# ChipStomp_v1_1.net
KiCad netlist of a schematic drawn in EAGLE
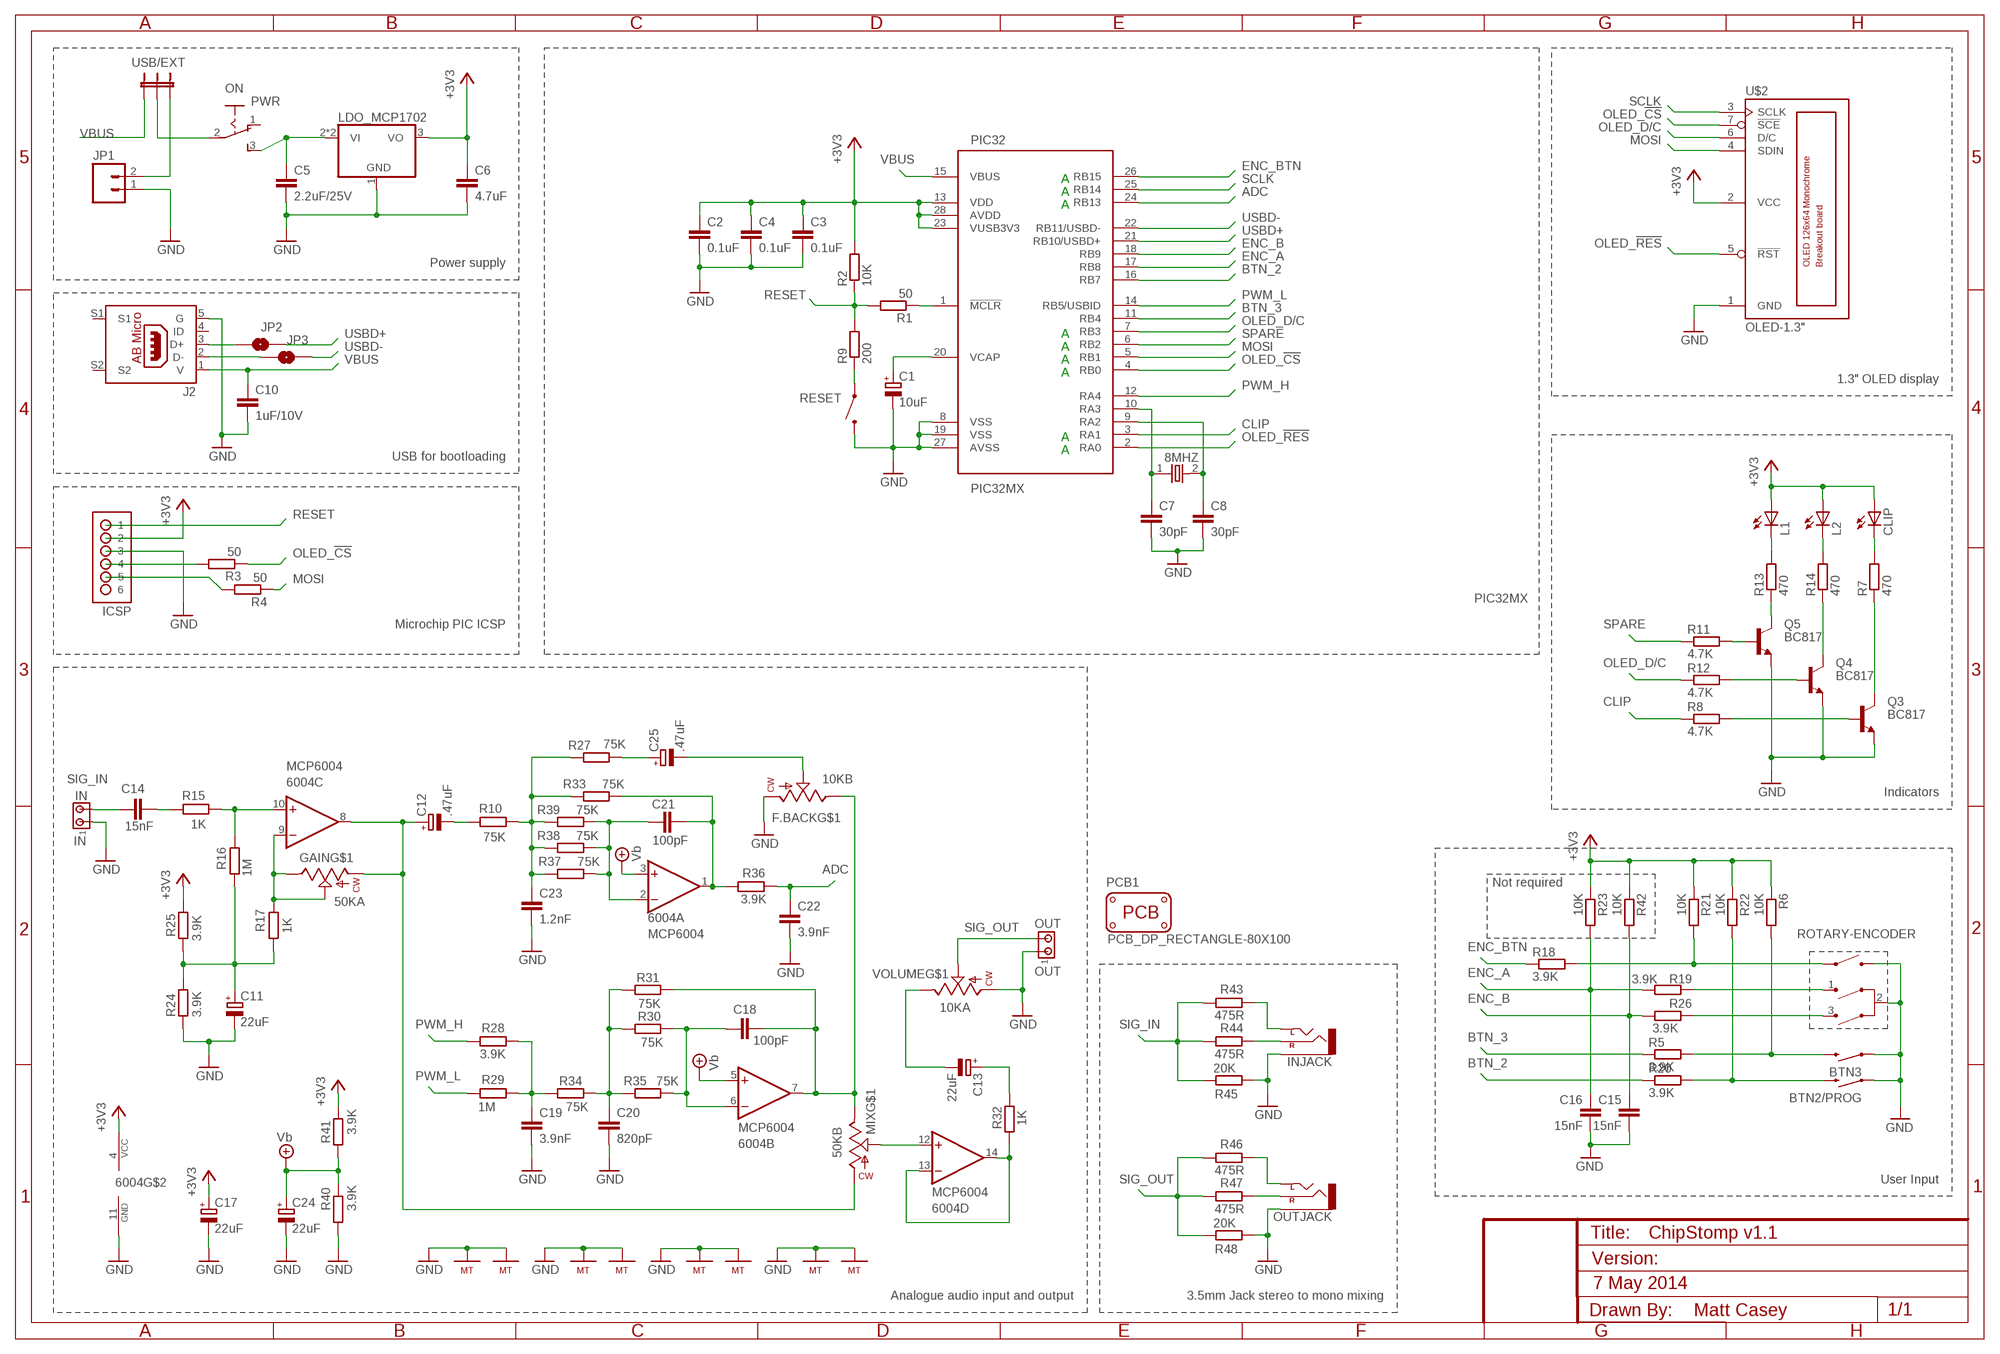
[diagram p0: schematic, sheet 1]

(export (version "E")
  (design (tool "Eeschema 10.0.6"))
  (components
    (comp (ref "8MHZ")
      (value "OSC-XTAL-HC-49U-SMD")
      (footprint "eagle-import:HC-49U")
      (libsource (lib "eagle-import") (part "OSC-XTAL-HC-49U-SMD"))
    )
    (comp (ref "6004")
      (value "MCP6004")
      (footprint "eagle-import:SO-14")
      (libsource (lib "eagle-import") (part "MCP6004"))
    )
    (comp (ref "BTN2/PROG")
      (value "SWITCH-MOMENTARY-212MM")
      (footprint "eagle-import:TACTILE-PTH-12MM")
      (libsource (lib "eagle-import") (part "SWITCH-MOMENTARY-212MM"))
    )
    (comp (ref "BTN3")
      (value "SWITCH-MOMENTARY-212MM")
      (footprint "eagle-import:TACTILE-PTH-12MM")
      (libsource (lib "eagle-import") (part "SWITCH-MOMENTARY-212MM"))
    )
    (comp (ref "C1")
      (value "10uF")
      (footprint "eagle-import:A_3216-18R")
      (libsource (lib "eagle-import") (part "CPOL-EUA/3216-18R"))
    )
    (comp (ref "C2")
      (value "0.1uF")
      (footprint "eagle-import:C0805K")
      (libsource (lib "eagle-import") (part "C-EUC0805K"))
    )
    (comp (ref "C3")
      (value "0.1uF")
      (footprint "eagle-import:C0805K")
      (libsource (lib "eagle-import") (part "C-EUC0805K"))
    )
    (comp (ref "C4")
      (value "0.1uF")
      (footprint "eagle-import:C0805K")
      (libsource (lib "eagle-import") (part "C-EUC0805K"))
    )
    (comp (ref "C5")
      (value "2.2uF/25V")
      (footprint "eagle-import:C0805K")
      (libsource (lib "eagle-import") (part "C-EUC0805K"))
    )
    (comp (ref "C6")
      (value "4.7uF")
      (footprint "eagle-import:C0805K")
      (libsource (lib "eagle-import") (part "C-EUC0805K"))
    )
    (comp (ref "C7")
      (value "30pF")
      (footprint "eagle-import:C0805K")
      (libsource (lib "eagle-import") (part "C-EUC0805K"))
    )
    (comp (ref "C8")
      (value "30pF")
      (footprint "eagle-import:C0805K")
      (libsource (lib "eagle-import") (part "C-EUC0805K"))
    )
    (comp (ref "C10")
      (value "1uF/10V")
      (footprint "eagle-import:C0805K")
      (libsource (lib "eagle-import") (part "C-EUC0805K"))
    )
    (comp (ref "C11")
      (value "22uF")
      (footprint "eagle-import:153CLV-0505")
      (libsource (lib "eagle-import") (part "CPOL-EU153CLV-0505"))
    )
    (comp (ref "C12")
      (value ".47uF")
      (footprint "eagle-import:153CLV-0405")
      (libsource (lib "eagle-import") (part "CPOL-EU153CLV-0405"))
    )
    (comp (ref "C13")
      (value "22uF")
      (footprint "eagle-import:153CLV-0505")
      (libsource (lib "eagle-import") (part "CPOL-EU153CLV-0505"))
    )
    (comp (ref "C14")
      (value "15nF")
      (footprint "eagle-import:C0805K")
      (libsource (lib "eagle-import") (part "C-EUC0805K"))
    )
    (comp (ref "C15")
      (value "15nF")
      (footprint "eagle-import:C0805K")
      (libsource (lib "eagle-import") (part "C-EUC0805K"))
    )
    (comp (ref "C16")
      (value "15nF")
      (footprint "eagle-import:C0805K")
      (libsource (lib "eagle-import") (part "C-EUC0805K"))
    )
    (comp (ref "C17")
      (value "22uF")
      (footprint "eagle-import:153CLV-0505")
      (libsource (lib "eagle-import") (part "CPOL-EU153CLV-0505"))
    )
    (comp (ref "C18")
      (value "100pF")
      (footprint "eagle-import:C0805K")
      (libsource (lib "eagle-import") (part "C-EUC0805K"))
    )
    (comp (ref "C19")
      (value "3.9nF")
      (footprint "eagle-import:C0805K")
      (libsource (lib "eagle-import") (part "C-EUC0805K"))
    )
    (comp (ref "C20")
      (value "820pF")
      (footprint "eagle-import:C0805K")
      (libsource (lib "eagle-import") (part "C-EUC0805K"))
    )
    (comp (ref "C21")
      (value "100pF")
      (footprint "eagle-import:C0805K")
      (libsource (lib "eagle-import") (part "C-EUC0805K"))
    )
    (comp (ref "C22")
      (value "3.9nF")
      (footprint "eagle-import:C0805K")
      (libsource (lib "eagle-import") (part "C-EUC0805K"))
    )
    (comp (ref "C23")
      (value "1.2nF")
      (footprint "eagle-import:C0805K")
      (libsource (lib "eagle-import") (part "C-EUC0805K"))
    )
    (comp (ref "C24")
      (value "22uF")
      (footprint "eagle-import:153CLV-0505")
      (libsource (lib "eagle-import") (part "CPOL-EU153CLV-0505"))
    )
    (comp (ref "C25")
      (value ".47uF")
      (footprint "eagle-import:153CLV-0405")
      (libsource (lib "eagle-import") (part "CPOL-EU153CLV-0405"))
    )
    (comp (ref "CLIP")
      (value "LED-0805")
      (footprint "eagle-import:LED-805")
      (libsource (lib "eagle-import") (part "LED-0805"))
    )
    (comp (ref "F.BACK")
      (value "10KB")
      (footprint "eagle-import:POT_SINGLE_PANASONIC_VERT")
      (libsource (lib "eagle-import") (part "POT"))
    )
    (comp (ref "GAIN")
      (value "50KA")
      (footprint "eagle-import:POT_SINGLE_PANASONIC_VERT")
      (libsource (lib "eagle-import") (part "POT"))
    )
    (comp (ref "ICSP")
      (value "No Load")
      (footprint "eagle-import:HDR-1X6_OFFSET")
      (libsource (lib "eagle-import") (part "HDR-1X6-OFFSET"))
    )
    (comp (ref "IN")
      (value "IN")
      (footprint "eagle-import:JMP_2P_SIP")
      (libsource (lib "eagle-import") (part "JMP/2P/SIP"))
    )
    (comp (ref "INJACK")
      (value "AUDIO-JACKPTH")
      (footprint "eagle-import:STEREO_JACK3.5MM_PTH")
      (libsource (lib "eagle-import") (part "AUDIO-JACKPTH"))
    )
    (comp (ref "J2")
      (value "US-AB-MICRO-TH")
      (footprint "eagle-import:WMRU2AB-05FLB2DSR-4.0")
      (libsource (lib "eagle-import") (part "US-AB-MICRO-TH"))
    )
    (comp (ref "JP1")
      (value "M023.5MM")
      (footprint "eagle-import:SCREWTERMINAL-3.5MM-2")
      (libsource (lib "eagle-import") (part "M023.5MM"))
    )
    (comp (ref "JP2")
      (value "Straight Male")
      (footprint "eagle-import:SJ_2S-TRACE")
      (libsource (lib "eagle-import") (part "SOLDERJUMPERTRACE"))
    )
    (comp (ref "JP3")
      (value "Straight Male")
      (footprint "eagle-import:SJ_2S-TRACE")
      (libsource (lib "eagle-import") (part "SOLDERJUMPERTRACE"))
    )
    (comp (ref "L1")
      (value "LED-0805")
      (footprint "eagle-import:LED-805")
      (libsource (lib "eagle-import") (part "LED-0805"))
    )
    (comp (ref "L2")
      (value "LED-0805")
      (footprint "eagle-import:LED-805")
      (libsource (lib "eagle-import") (part "LED-0805"))
    )
    (comp (ref "MIX")
      (value "50KB")
      (footprint "eagle-import:POT_SINGLE_PANASONIC_VERT")
      (libsource (lib "eagle-import") (part "POT"))
    )
    (comp (ref "ON")
      (value "PWR")
      (footprint "eagle-import:DX_MINI_SPDT_VERTICAL")
      (libsource (lib "eagle-import") (part "DX_MINI_SPDT"))
    )
    (comp (ref "OUT")
      (value "OUT")
      (footprint "eagle-import:JMP_2P_SIP")
      (libsource (lib "eagle-import") (part "JMP/2P/SIP"))
    )
    (comp (ref "OUTJACK")
      (value "AUDIO-JACKPTH")
      (footprint "eagle-import:STEREO_JACK3.5MM_PTH")
      (libsource (lib "eagle-import") (part "AUDIO-JACKPTH"))
    )
    (comp (ref "PCB1")
      (value "PCB_DP_RECTANGLE-80X100")
      (footprint "eagle-import:DP10080_V1")
      (libsource (lib "eagle-import") (part "PCB_DP_RECTANGLE-80X100"))
    )
    (comp (ref "PIC32")
      (value "PIC32MX")
      (footprint "eagle-import:SO-28")
      (libsource (lib "eagle-import") (part "PIC32MX250FXXXB"))
    )
    (comp (ref "Q3")
      (value "BC817")
      (footprint "eagle-import:SOT23-BEC")
      (libsource (lib "eagle-import") (part "BC817SMD-16LT1"))
    )
    (comp (ref "Q4")
      (value "BC817")
      (footprint "eagle-import:SOT23-BEC")
      (libsource (lib "eagle-import") (part "BC817SMD-16LT1"))
    )
    (comp (ref "Q5")
      (value "BC817")
      (footprint "eagle-import:SOT23-BEC")
      (libsource (lib "eagle-import") (part "BC817SMD-16LT1"))
    )
    (comp (ref "R1")
      (value "50")
      (footprint "eagle-import:R0805")
      (libsource (lib "eagle-import") (part "R-EU_R0805"))
    )
    (comp (ref "R2")
      (value "10K")
      (footprint "eagle-import:R0805")
      (libsource (lib "eagle-import") (part "R-EU_R0805"))
    )
    (comp (ref "R3")
      (value "50")
      (footprint "eagle-import:R0805")
      (libsource (lib "eagle-import") (part "R-EU_R0805"))
    )
    (comp (ref "R4")
      (value "50")
      (footprint "eagle-import:R0805")
      (libsource (lib "eagle-import") (part "R-EU_R0805"))
    )
    (comp (ref "R5")
      (value "3.9K")
      (footprint "eagle-import:R0805")
      (libsource (lib "eagle-import") (part "R-EU_R0805"))
    )
    (comp (ref "R6")
      (value "10K")
      (footprint "eagle-import:R0805")
      (libsource (lib "eagle-import") (part "R-EU_R0805"))
    )
    (comp (ref "R7")
      (value "470")
      (footprint "eagle-import:R0805")
      (libsource (lib "eagle-import") (part "R-EU_R0805"))
    )
    (comp (ref "R8")
      (value "4.7K")
      (footprint "eagle-import:R0805")
      (libsource (lib "eagle-import") (part "R-EU_R0805"))
    )
    (comp (ref "R9")
      (value "200")
      (footprint "eagle-import:R0805")
      (libsource (lib "eagle-import") (part "R-EU_R0805"))
    )
    (comp (ref "R10")
      (value "75K")
      (footprint "eagle-import:R0805")
      (libsource (lib "eagle-import") (part "R-EU_R0805"))
    )
    (comp (ref "R11")
      (value "4.7K")
      (footprint "eagle-import:R0805")
      (libsource (lib "eagle-import") (part "R-EU_R0805"))
    )
    (comp (ref "R12")
      (value "4.7K")
      (footprint "eagle-import:R0805")
      (libsource (lib "eagle-import") (part "R-EU_R0805"))
    )
    (comp (ref "R13")
      (value "470")
      (footprint "eagle-import:R0805")
      (libsource (lib "eagle-import") (part "R-EU_R0805"))
    )
    (comp (ref "R14")
      (value "470")
      (footprint "eagle-import:R0805")
      (libsource (lib "eagle-import") (part "R-EU_R0805"))
    )
    (comp (ref "R15")
      (value "1K")
      (footprint "eagle-import:R0805")
      (libsource (lib "eagle-import") (part "R-EU_R0805"))
    )
    (comp (ref "R16")
      (value "1M")
      (footprint "eagle-import:R0805")
      (libsource (lib "eagle-import") (part "R-EU_R0805"))
    )
    (comp (ref "R17")
      (value "1K")
      (footprint "eagle-import:R0805")
      (libsource (lib "eagle-import") (part "R-EU_R0805"))
    )
    (comp (ref "R18")
      (value "3.9K")
      (footprint "eagle-import:R0805")
      (libsource (lib "eagle-import") (part "R-EU_R0805"))
    )
    (comp (ref "R19")
      (value "3.9K")
      (footprint "eagle-import:R0805")
      (libsource (lib "eagle-import") (part "R-EU_R0805"))
    )
    (comp (ref "R20")
      (value "3.9K")
      (footprint "eagle-import:R0805")
      (libsource (lib "eagle-import") (part "R-EU_R0805"))
    )
    (comp (ref "R21")
      (value "10K")
      (footprint "eagle-import:R0805")
      (libsource (lib "eagle-import") (part "R-EU_R0805"))
    )
    (comp (ref "R22")
      (value "10K")
      (footprint "eagle-import:R0805")
      (libsource (lib "eagle-import") (part "R-EU_R0805"))
    )
    (comp (ref "R23")
      (value "10K")
      (footprint "eagle-import:R0805")
      (libsource (lib "eagle-import") (part "R-EU_R0805"))
    )
    (comp (ref "R24")
      (value "3.9K")
      (footprint "eagle-import:R0805")
      (libsource (lib "eagle-import") (part "R-EU_R0805"))
    )
    (comp (ref "R25")
      (value "3.9K")
      (footprint "eagle-import:R0805")
      (libsource (lib "eagle-import") (part "R-EU_R0805"))
    )
    (comp (ref "R26")
      (value "3.9K")
      (footprint "eagle-import:R0805")
      (libsource (lib "eagle-import") (part "R-EU_R0805"))
    )
    (comp (ref "R27")
      (value "75K")
      (footprint "eagle-import:R0805")
      (libsource (lib "eagle-import") (part "R-EU_R0805"))
    )
    (comp (ref "R28")
      (value "3.9K")
      (footprint "eagle-import:R0805")
      (libsource (lib "eagle-import") (part "R-EU_R0805"))
    )
    (comp (ref "R29")
      (value "1M")
      (footprint "eagle-import:R0805")
      (libsource (lib "eagle-import") (part "R-EU_R0805"))
    )
    (comp (ref "R30")
      (value "75K")
      (footprint "eagle-import:R0805")
      (libsource (lib "eagle-import") (part "R-EU_R0805"))
    )
    (comp (ref "R31")
      (value "75K")
      (footprint "eagle-import:R0805")
      (libsource (lib "eagle-import") (part "R-EU_R0805"))
    )
    (comp (ref "R32")
      (value "1K")
      (footprint "eagle-import:R0805")
      (libsource (lib "eagle-import") (part "R-EU_R0805"))
    )
    (comp (ref "R33")
      (value "75K")
      (footprint "eagle-import:R0805")
      (libsource (lib "eagle-import") (part "R-EU_R0805"))
    )
    (comp (ref "R34")
      (value "75K")
      (footprint "eagle-import:R0805")
      (libsource (lib "eagle-import") (part "R-EU_R0805"))
    )
    (comp (ref "R35")
      (value "75K")
      (footprint "eagle-import:R0805")
      (libsource (lib "eagle-import") (part "R-EU_R0805"))
    )
    (comp (ref "R36")
      (value "3.9K")
      (footprint "eagle-import:R0805")
      (libsource (lib "eagle-import") (part "R-EU_R0805"))
    )
    (comp (ref "R37")
      (value "75K")
      (footprint "eagle-import:R0805")
      (libsource (lib "eagle-import") (part "R-EU_R0805"))
    )
    (comp (ref "R38")
      (value "75K")
      (footprint "eagle-import:R0805")
      (libsource (lib "eagle-import") (part "R-EU_R0805"))
    )
    (comp (ref "R39")
      (value "75K")
      (footprint "eagle-import:R0805")
      (libsource (lib "eagle-import") (part "R-EU_R0805"))
    )
    (comp (ref "R40")
      (value "3.9K")
      (footprint "eagle-import:R0805")
      (libsource (lib "eagle-import") (part "R-EU_R0805"))
    )
    (comp (ref "R41")
      (value "3.9K")
      (footprint "eagle-import:R0805")
      (libsource (lib "eagle-import") (part "R-EU_R0805"))
    )
    (comp (ref "R42")
      (value "10K")
      (footprint "eagle-import:R0805")
      (libsource (lib "eagle-import") (part "R-EU_R0805"))
    )
    (comp (ref "R43")
      (value "475R")
      (footprint "eagle-import:R0805")
      (libsource (lib "eagle-import") (part "R-EU_R0805"))
    )
    (comp (ref "R44")
      (value "475R")
      (footprint "eagle-import:R0805")
      (libsource (lib "eagle-import") (part "R-EU_R0805"))
    )
    (comp (ref "R45")
      (value "20K")
      (footprint "eagle-import:R0805")
      (libsource (lib "eagle-import") (part "R-EU_R0805"))
    )
    (comp (ref "R46")
      (value "475R")
      (footprint "eagle-import:R0805")
      (libsource (lib "eagle-import") (part "R-EU_R0805"))
    )
    (comp (ref "R47")
      (value "475R")
      (footprint "eagle-import:R0805")
      (libsource (lib "eagle-import") (part "R-EU_R0805"))
    )
    (comp (ref "R48")
      (value "20K")
      (footprint "eagle-import:R0805")
      (libsource (lib "eagle-import") (part "R-EU_R0805"))
    )
    (comp (ref "RESET")
      (value "TINY_TACTILEPTH")
      (footprint "eagle-import:TINY_TACTILE_PTH")
      (libsource (lib "eagle-import") (part "TINY_TACTILEPTH"))
    )
    (comp (ref "SW1")
      (value "ROTARY-ENCODER")
      (footprint "eagle-import:SURE")
      (libsource (lib "eagle-import") (part "ROTARY-ENCODER"))
    )
    (comp (ref "U$2")
      (value "OLED-1.3\"")
      (footprint "eagle-import:OLED-130-BREAKOUT_2HOLES")
      (libsource (lib "eagle-import") (part "OLED-130-BREAKOUT2HOLES"))
    )
    (comp (ref "U$3")
      (value "LDO_MCP1702")
      (footprint "eagle-import:SOT89")
      (libsource (lib "eagle-import") (part "LDO_MCP1702SOT89"))
    )
    (comp (ref "USB/EXT")
      (value "JUMPER-3PTH")
      (footprint "eagle-import:1X03")
      (libsource (lib "eagle-import") (part "JUMPER-3PTH"))
    )
    (comp (ref "VOLUME")
      (value "10KA")
      (footprint "eagle-import:POT_SINGLE_PANASONIC_VERT")
      (libsource (lib "eagle-import") (part "POT"))
    )
  )
  (nets
    (net (code "1") (name "+3V3") (class "Default")
      (node (ref "6004") (pin "4") (pinfunction "VCC_4") (pintype "power_in"))
      (node (ref "C17") (pin "+") (pinfunction "+_+") (pintype "passive"))
      (node (ref "C2") (pin "1") (pinfunction "1_1") (pintype "passive"))
      (node (ref "C3") (pin "1") (pinfunction "1_1") (pintype "passive"))
      (node (ref "C4") (pin "1") (pinfunction "1_1") (pintype "passive"))
      (node (ref "C6") (pin "1") (pinfunction "1_1") (pintype "passive"))
      (node (ref "CLIP") (pin "A") (pinfunction "A_A") (pintype "passive"))
      (node (ref "ICSP") (pin "2") (pinfunction "2_2") (pintype "passive"))
      (node (ref "L1") (pin "A") (pinfunction "A_A") (pintype "passive"))
      (node (ref "L2") (pin "A") (pinfunction "A_A") (pintype "passive"))
      (node (ref "PIC32") (pin "13") (pinfunction "VDD_13") (pintype "power_in"))
      (node (ref "PIC32") (pin "23") (pinfunction "VUSB3V3_23") (pintype "power_in"))
      (node (ref "PIC32") (pin "28") (pinfunction "AVDD_28") (pintype "power_in"))
      (node (ref "R2") (pin "2") (pinfunction "2_2") (pintype "passive"))
      (node (ref "R21") (pin "1") (pinfunction "1_1") (pintype "passive"))
      (node (ref "R22") (pin "1") (pinfunction "1_1") (pintype "passive"))
      (node (ref "R23") (pin "1") (pinfunction "1_1") (pintype "passive"))
      (node (ref "R25") (pin "1") (pinfunction "1_1") (pintype "passive"))
      (node (ref "R41") (pin "1") (pinfunction "1_1") (pintype "passive"))
      (node (ref "R42") (pin "1") (pinfunction "1_1") (pintype "passive"))
      (node (ref "R6") (pin "1") (pinfunction "1_1") (pintype "passive"))
      (node (ref "U$2") (pin "2") (pinfunction "VCC_2") (pintype "power_in"))
      (node (ref "U$3") (pin "3") (pinfunction "VO_3") (pintype "power_in"))
    )
    (net (code "2") (name "/ADC") (class "Default")
      (node (ref "C22") (pin "1") (pinfunction "1_1") (pintype "passive"))
      (node (ref "PIC32") (pin "24") (pinfunction "RB13_24") (pintype "bidirectional"))
      (node (ref "R36") (pin "1") (pinfunction "1_1") (pintype "passive"))
    )
    (net (code "3") (name "/BTN_2") (class "Default")
      (node (ref "PIC32") (pin "16") (pinfunction "RB7_16") (pintype "bidirectional"))
      (node (ref "R20") (pin "1") (pinfunction "1_1") (pintype "passive"))
    )
    (net (code "4") (name "/BTN_3") (class "Default")
      (node (ref "PIC32") (pin "11") (pinfunction "RB4_11") (pintype "bidirectional"))
      (node (ref "R5") (pin "1") (pinfunction "1_1") (pintype "passive"))
    )
    (net (code "5") (name "/CLIP") (class "Default")
      (node (ref "PIC32") (pin "3") (pinfunction "RA1_3") (pintype "bidirectional"))
      (node (ref "R8") (pin "1") (pinfunction "1_1") (pintype "passive"))
    )
    (net (code "6") (name "/ENC_A") (class "Default")
      (node (ref "C16") (pin "1") (pinfunction "1_1") (pintype "passive"))
      (node (ref "PIC32") (pin "17") (pinfunction "RB8_17") (pintype "input"))
      (node (ref "R19") (pin "1") (pinfunction "1_1") (pintype "passive"))
      (node (ref "R23") (pin "2") (pinfunction "2_2") (pintype "passive"))
    )
    (net (code "7") (name "/ENC_B") (class "Default")
      (node (ref "C15") (pin "1") (pinfunction "1_1") (pintype "passive"))
      (node (ref "PIC32") (pin "18") (pinfunction "RB9_18") (pintype "bidirectional"))
      (node (ref "R26") (pin "1") (pinfunction "1_1") (pintype "passive"))
      (node (ref "R42") (pin "2") (pinfunction "2_2") (pintype "passive"))
    )
    (net (code "8") (name "/ENC_BTN") (class "Default")
      (node (ref "PIC32") (pin "26") (pinfunction "RB15_26") (pintype "bidirectional"))
      (node (ref "R18") (pin "1") (pinfunction "1_1") (pintype "passive"))
    )
    (net (code "9") (name "/MOSI") (class "Default")
      (node (ref "PIC32") (pin "5") (pinfunction "RB1_5") (pintype "bidirectional"))
      (node (ref "R4") (pin "1") (pinfunction "1_1") (pintype "passive"))
      (node (ref "U$2") (pin "4") (pinfunction "SDIN_4") (pintype "input"))
    )
    (net (code "10") (name "/OLED_D{slash}C") (class "Default")
      (node (ref "PIC32") (pin "7") (pinfunction "RB3_7") (pintype "bidirectional"))
      (node (ref "R12") (pin "1") (pinfunction "1_1") (pintype "passive"))
      (node (ref "U$2") (pin "6") (pinfunction "D/C_6") (pintype "input"))
    )
    (net (code "11") (name "/OLED_~{CS}") (class "Default")
      (node (ref "PIC32") (pin "4") (pinfunction "RB0_4") (pintype "bidirectional"))
      (node (ref "R3") (pin "1") (pinfunction "1_1") (pintype "passive"))
      (node (ref "U$2") (pin "7") (pinfunction "~{SCE}_7") (pintype "input"))
    )
    (net (code "12") (name "/OLED_~{RES}") (class "Default")
      (node (ref "PIC32") (pin "2") (pinfunction "RA0_2") (pintype "bidirectional"))
      (node (ref "U$2") (pin "5") (pinfunction "~{RST}_5") (pintype "input"))
    )
    (net (code "13") (name "/PWM_H") (class "Default")
      (node (ref "PIC32") (pin "12") (pinfunction "RA4_12") (pintype "bidirectional"))
      (node (ref "R28") (pin "2") (pinfunction "2_2") (pintype "passive"))
    )
    (net (code "14") (name "/PWM_L") (class "Default")
      (node (ref "PIC32") (pin "14") (pinfunction "RB5/USBID_14") (pintype "bidirectional"))
      (node (ref "R29") (pin "2") (pinfunction "2_2") (pintype "passive"))
    )
    (net (code "15") (name "/RESET") (class "Default")
      (node (ref "ICSP") (pin "1") (pinfunction "1_1") (pintype "passive"))
      (node (ref "R1") (pin "2") (pinfunction "2_2") (pintype "passive"))
      (node (ref "R2") (pin "1") (pinfunction "1_1") (pintype "passive"))
      (node (ref "R9") (pin "2") (pinfunction "2_2") (pintype "passive"))
    )
    (net (code "16") (name "/SCLK") (class "Default")
      (node (ref "PIC32") (pin "25") (pinfunction "RB14_25") (pintype "bidirectional"))
      (node (ref "U$2") (pin "3") (pinfunction "SCLK_3") (pintype "input"))
    )
    (net (code "17") (name "/SIG_IN") (class "Default")
      (node (ref "C14") (pin "1") (pinfunction "1_1") (pintype "passive"))
      (node (ref "IN") (pin "2") (pinfunction "2_2") (pintype "passive"))
      (node (ref "R43") (pin "2") (pinfunction "2_2") (pintype "passive"))
      (node (ref "R44") (pin "2") (pinfunction "2_2") (pintype "passive"))
      (node (ref "R45") (pin "1") (pinfunction "1_1") (pintype "passive"))
    )
    (net (code "18") (name "/SIG_OUT") (class "Default")
      (node (ref "OUT") (pin "2") (pinfunction "2_2") (pintype "passive"))
      (node (ref "R46") (pin "2") (pinfunction "2_2") (pintype "passive"))
      (node (ref "R47") (pin "2") (pinfunction "2_2") (pintype "passive"))
      (node (ref "R48") (pin "1") (pinfunction "1_1") (pintype "passive"))
      (node (ref "VOLUME") (pin "P$2") (pinfunction "2_P$2") (pintype "passive"))
    )
    (net (code "19") (name "/SPARE") (class "Default")
      (node (ref "PIC32") (pin "6") (pinfunction "RB2_6") (pintype "bidirectional"))
      (node (ref "R11") (pin "1") (pinfunction "1_1") (pintype "passive"))
    )
    (net (code "20") (name "/USBD+") (class "Default")
      (node (ref "J2") (pin "3") (pinfunction "D+_3") (pintype "bidirectional"))
      (node (ref "JP2") (pin "1") (pinfunction "1_1") (pintype "passive"))
      (node (ref "JP2") (pin "2") (pinfunction "2_2") (pintype "passive"))
      (node (ref "PIC32") (pin "21") (pinfunction "RB10/USBD+_21") (pintype "bidirectional"))
    )
    (net (code "21") (name "/USBD-") (class "Default")
      (node (ref "JP3") (pin "2") (pinfunction "2_2") (pintype "passive"))
      (node (ref "PIC32") (pin "22") (pinfunction "RB11/USBD-_22") (pintype "bidirectional"))
    )
    (net (code "22") (name "/VBUS") (class "Default")
      (node (ref "C10") (pin "1") (pinfunction "1_1") (pintype "passive"))
      (node (ref "J2") (pin "1") (pinfunction "V_1") (pintype "bidirectional"))
      (node (ref "PIC32") (pin "15") (pinfunction "VBUS_15") (pintype "power_in"))
      (node (ref "USB/EXT") (pin "1") (pinfunction "1_1") (pintype "passive"))
    )
    (net (code "23") (name "GND") (class "Default")
      (node (ref "6004") (pin "11") (pinfunction "GND_11") (pintype "power_in"))
      (node (ref "BTN2/PROG") (pin "1") (pinfunction "1_1") (pintype "passive"))
      (node (ref "BTN3") (pin "1") (pinfunction "1_1") (pintype "passive"))
      (node (ref "C1") (pin "-") (pinfunction "-_-") (pintype "passive"))
      (node (ref "C10") (pin "2") (pinfunction "2_2") (pintype "passive"))
      (node (ref "C11") (pin "-") (pinfunction "-_-") (pintype "passive"))
      (node (ref "C15") (pin "2") (pinfunction "2_2") (pintype "passive"))
      (node (ref "C16") (pin "2") (pinfunction "2_2") (pintype "passive"))
      (node (ref "C17") (pin "-") (pinfunction "-_-") (pintype "passive"))
      (node (ref "C19") (pin "2") (pinfunction "2_2") (pintype "passive"))
      (node (ref "C2") (pin "2") (pinfunction "2_2") (pintype "passive"))
      (node (ref "C20") (pin "2") (pinfunction "2_2") (pintype "passive"))
      (node (ref "C22") (pin "2") (pinfunction "2_2") (pintype "passive"))
      (node (ref "C23") (pin "2") (pinfunction "2_2") (pintype "passive"))
      (node (ref "C24") (pin "-") (pinfunction "-_-") (pintype "passive"))
      (node (ref "C3") (pin "2") (pinfunction "2_2") (pintype "passive"))
      (node (ref "C4") (pin "2") (pinfunction "2_2") (pintype "passive"))
      (node (ref "C5") (pin "2") (pinfunction "2_2") (pintype "passive"))
      (node (ref "C6") (pin "2") (pinfunction "2_2") (pintype "passive"))
      (node (ref "C7") (pin "2") (pinfunction "2_2") (pintype "passive"))
      (node (ref "C8") (pin "2") (pinfunction "2_2") (pintype "passive"))
      (node (ref "F.BACK") (pin "P$1") (pinfunction "1_P$1") (pintype "passive"))
      (node (ref "F.BACK") (pin "P$4") (pinfunction "MT_P$4") (pintype "passive"))
      (node (ref "F.BACK") (pin "P$5") (pinfunction "MT_P$5") (pintype "passive"))
      (node (ref "GAIN") (pin "P$4") (pinfunction "MT_P$4") (pintype "passive"))
      (node (ref "GAIN") (pin "P$5") (pinfunction "MT_P$5") (pintype "passive"))
      (node (ref "ICSP") (pin "3") (pinfunction "3_3") (pintype "passive"))
      (node (ref "IN") (pin "1") (pinfunction "1_1") (pintype "passive"))
      (node (ref "INJACK") (pin "S") (pinfunction "SLEEVE_S") (pintype "bidirectional"))
      (node (ref "INJACK") (pin "S@1") (pinfunction "SLEEVE_S@1") (pintype "bidirectional"))
      (node (ref "J2") (pin "5") (pinfunction "G_5") (pintype "bidirectional"))
      (node (ref "JP1") (pin "1") (pinfunction "1_1") (pintype "passive"))
      (node (ref "MIX") (pin "P$4") (pinfunction "MT_P$4") (pintype "passive"))
      (node (ref "MIX") (pin "P$5") (pinfunction "MT_P$5") (pintype "passive"))
      (node (ref "OUT") (pin "1") (pinfunction "1_1") (pintype "passive"))
      (node (ref "OUTJACK") (pin "S") (pinfunction "SLEEVE_S") (pintype "bidirectional"))
      (node (ref "OUTJACK") (pin "S@1") (pinfunction "SLEEVE_S@1") (pintype "bidirectional"))
      (node (ref "PIC32") (pin "19") (pinfunction "VSS_19") (pintype "power_in"))
      (node (ref "PIC32") (pin "27") (pinfunction "AVSS_27") (pintype "power_in"))
      (node (ref "PIC32") (pin "8") (pinfunction "VSS_8") (pintype "power_in"))
      (node (ref "Q3") (pin "E") (pinfunction "E_E") (pintype "passive"))
      (node (ref "Q4") (pin "E") (pinfunction "E_E") (pintype "passive"))
      (node (ref "Q5") (pin "E") (pinfunction "E_E") (pintype "passive"))
      (node (ref "R24") (pin "2") (pinfunction "2_2") (pintype "passive"))
      (node (ref "R40") (pin "2") (pinfunction "2_2") (pintype "passive"))
      (node (ref "R45") (pin "2") (pinfunction "2_2") (pintype "passive"))
      (node (ref "R48") (pin "2") (pinfunction "2_2") (pintype "passive"))
      (node (ref "RESET") (pin "2") (pinfunction "B_2") (pintype "passive"))
      (node (ref "SW1") (pin "2") (pinfunction "COMMON_2") (pintype "passive"))
      (node (ref "SW1") (pin "A") (pinfunction "B_A") (pintype "passive"))
      (node (ref "U$2") (pin "1") (pinfunction "GND_1") (pintype "power_in"))
      (node (ref "U$3") (pin "1") (pinfunction "GND_1") (pintype "input"))
      (node (ref "VOLUME") (pin "P$1") (pinfunction "1_P$1") (pintype "passive"))
      (node (ref "VOLUME") (pin "P$4") (pinfunction "MT_P$4") (pintype "passive"))
      (node (ref "VOLUME") (pin "P$5") (pinfunction "MT_P$5") (pintype "passive"))
    )
    (net (code "24") (name "Net-(6004A--IN)") (class "Default")
      (node (ref "6004") (pin "2") (pinfunction "-IN_2") (pintype "input"))
      (node (ref "C21") (pin "1") (pinfunction "1_1") (pintype "passive"))
      (node (ref "R37") (pin "1") (pinfunction "1_1") (pintype "passive"))
      (node (ref "R38") (pin "1") (pinfunction "1_1") (pintype "passive"))
      (node (ref "R39") (pin "1") (pinfunction "1_1") (pintype "passive"))
    )
    (net (code "25") (name "Net-(6004A-OUT)") (class "Default")
      (node (ref "6004") (pin "1") (pinfunction "OUT_1") (pintype "output"))
      (node (ref "C21") (pin "2") (pinfunction "2_2") (pintype "passive"))
      (node (ref "R33") (pin "1") (pinfunction "1_1") (pintype "passive"))
      (node (ref "R36") (pin "2") (pinfunction "2_2") (pintype "passive"))
    )
    (net (code "26") (name "Net-(6004B--IN)") (class "Default")
      (node (ref "6004") (pin "6") (pinfunction "-IN_6") (pintype "input"))
      (node (ref "C18") (pin "1") (pinfunction "1_1") (pintype "passive"))
      (node (ref "R30") (pin "1") (pinfunction "1_1") (pintype "passive"))
      (node (ref "R35") (pin "1") (pinfunction "1_1") (pintype "passive"))
    )
    (net (code "27") (name "Net-(6004B-OUT)") (class "Default")
      (node (ref "6004") (pin "7") (pinfunction "OUT_7") (pintype "output"))
      (node (ref "C18") (pin "2") (pinfunction "2_2") (pintype "passive"))
      (node (ref "F.BACK") (pin "P$3") (pinfunction "3_P$3") (pintype "passive"))
      (node (ref "MIX") (pin "P$3") (pinfunction "3_P$3") (pintype "passive"))
      (node (ref "R31") (pin "1") (pinfunction "1_1") (pintype "passive"))
    )
    (net (code "28") (name "Net-(6004C-+IN)") (class "Default")
      (node (ref "6004") (pin "10") (pinfunction "+IN_10") (pintype "input"))
      (node (ref "R15") (pin "1") (pinfunction "1_1") (pintype "passive"))
      (node (ref "R16") (pin "2") (pinfunction "2_2") (pintype "passive"))
    )
    (net (code "29") (name "Net-(6004C--IN)") (class "Default")
      (node (ref "6004") (pin "9") (pinfunction "-IN_9") (pintype "input"))
      (node (ref "GAIN") (pin "P$2") (pinfunction "2_P$2") (pintype "passive"))
      (node (ref "GAIN") (pin "P$3") (pinfunction "3_P$3") (pintype "passive"))
      (node (ref "R17") (pin "2") (pinfunction "2_2") (pintype "passive"))
    )
    (net (code "30") (name "Net-(6004C-OUT)") (class "Default")
      (node (ref "6004") (pin "8") (pinfunction "OUT_8") (pintype "output"))
      (node (ref "C12") (pin "+") (pinfunction "+_+") (pintype "passive"))
      (node (ref "GAIN") (pin "P$1") (pinfunction "1_P$1") (pintype "passive"))
      (node (ref "MIX") (pin "P$1") (pinfunction "1_P$1") (pintype "passive"))
    )
    (net (code "31") (name "Net-(6004D-+IN)") (class "Default")
      (node (ref "6004") (pin "12") (pinfunction "+IN_12") (pintype "input"))
      (node (ref "MIX") (pin "P$2") (pinfunction "2_P$2") (pintype "passive"))
    )
    (net (code "32") (name "Net-(6004D--IN)") (class "Default")
      (node (ref "6004") (pin "13") (pinfunction "-IN_13") (pintype "input"))
      (node (ref "6004") (pin "14") (pinfunction "OUT_14") (pintype "output"))
      (node (ref "R32") (pin "2") (pinfunction "2_2") (pintype "passive"))
    )
    (net (code "33") (name "Net-(BTN2/PROG-2)") (class "Default")
      (node (ref "BTN2/PROG") (pin "3") (pinfunction "2_3") (pintype "passive"))
      (node (ref "R20") (pin "2") (pinfunction "2_2") (pintype "passive"))
      (node (ref "R22") (pin "2") (pinfunction "2_2") (pintype "passive"))
    )
    (net (code "34") (name "Net-(BTN3-2)") (class "Default")
      (node (ref "BTN3") (pin "3") (pinfunction "2_3") (pintype "passive"))
      (node (ref "R5") (pin "2") (pinfunction "2_2") (pintype "passive"))
      (node (ref "R6") (pin "2") (pinfunction "2_2") (pintype "passive"))
    )
    (net (code "35") (name "Net-(C11-Pad+)") (class "Default")
      (node (ref "C11") (pin "+") (pinfunction "+_+") (pintype "passive"))
      (node (ref "R16") (pin "1") (pinfunction "1_1") (pintype "passive"))
      (node (ref "R17") (pin "1") (pinfunction "1_1") (pintype "passive"))
      (node (ref "R24") (pin "1") (pinfunction "1_1") (pintype "passive"))
      (node (ref "R25") (pin "2") (pinfunction "2_2") (pintype "passive"))
    )
    (net (code "36") (name "Net-(C12-Pad-)") (class "Default")
      (node (ref "C12") (pin "-") (pinfunction "-_-") (pintype "passive"))
      (node (ref "R10") (pin "2") (pinfunction "2_2") (pintype "passive"))
    )
    (net (code "37") (name "Net-(C13-Pad+)") (class "Default")
      (node (ref "C13") (pin "+") (pinfunction "+_+") (pintype "passive"))
      (node (ref "R32") (pin "1") (pinfunction "1_1") (pintype "passive"))
    )
    (net (code "38") (name "Net-(C14-Pad2)") (class "Default")
      (node (ref "C14") (pin "2") (pinfunction "2_2") (pintype "passive"))
      (node (ref "R15") (pin "2") (pinfunction "2_2") (pintype "passive"))
    )
    (net (code "39") (name "Net-(C19-Pad1)") (class "Default")
      (node (ref "C19") (pin "1") (pinfunction "1_1") (pintype "passive"))
      (node (ref "R28") (pin "1") (pinfunction "1_1") (pintype "passive"))
      (node (ref "R29") (pin "1") (pinfunction "1_1") (pintype "passive"))
      (node (ref "R34") (pin "2") (pinfunction "2_2") (pintype "passive"))
    )
    (net (code "40") (name "Net-(C20-Pad1)") (class "Default")
      (node (ref "C20") (pin "1") (pinfunction "1_1") (pintype "passive"))
      (node (ref "R30") (pin "2") (pinfunction "2_2") (pintype "passive"))
      (node (ref "R31") (pin "2") (pinfunction "2_2") (pintype "passive"))
      (node (ref "R34") (pin "1") (pinfunction "1_1") (pintype "passive"))
      (node (ref "R35") (pin "2") (pinfunction "2_2") (pintype "passive"))
    )
    (net (code "41") (name "Net-(C23-Pad1)") (class "Default")
      (node (ref "C23") (pin "1") (pinfunction "1_1") (pintype "passive"))
      (node (ref "R10") (pin "1") (pinfunction "1_1") (pintype "passive"))
      (node (ref "R27") (pin "2") (pinfunction "2_2") (pintype "passive"))
      (node (ref "R33") (pin "2") (pinfunction "2_2") (pintype "passive"))
      (node (ref "R37") (pin "2") (pinfunction "2_2") (pintype "passive"))
      (node (ref "R38") (pin "2") (pinfunction "2_2") (pintype "passive"))
      (node (ref "R39") (pin "2") (pinfunction "2_2") (pintype "passive"))
    )
    (net (code "42") (name "Net-(C25-Pad+)") (class "Default")
      (node (ref "C25") (pin "+") (pinfunction "+_+") (pintype "passive"))
      (node (ref "R27") (pin "1") (pinfunction "1_1") (pintype "passive"))
    )
    (net (code "43") (name "Net-(CLIP-PadC)") (class "Default")
      (node (ref "CLIP") (pin "C") (pinfunction "C_C") (pintype "passive"))
      (node (ref "R7") (pin "2") (pinfunction "2_2") (pintype "passive"))
    )
    (net (code "44") (name "Net-(F.BACKA-2)") (class "Default")
      (node (ref "C25") (pin "-") (pinfunction "-_-") (pintype "passive"))
      (node (ref "F.BACK") (pin "P$2") (pinfunction "2_P$2") (pintype "passive"))
    )
    (net (code "45") (name "Net-(ICSP-Pad4)") (class "Default")
      (node (ref "ICSP") (pin "4") (pinfunction "4_4") (pintype "passive"))
      (node (ref "R3") (pin "2") (pinfunction "2_2") (pintype "passive"))
    )
    (net (code "46") (name "Net-(ICSP-Pad5)") (class "Default")
      (node (ref "ICSP") (pin "5") (pinfunction "5_5") (pintype "passive"))
      (node (ref "R4") (pin "2") (pinfunction "2_2") (pintype "passive"))
    )
    (net (code "47") (name "Net-(INJACK-LEFT-PadL)") (class "Default")
      (node (ref "INJACK") (pin "L") (pinfunction "LEFT_L") (pintype "bidirectional"))
      (node (ref "INJACK") (pin "L@1") (pinfunction "LEFT_L@1") (pintype "bidirectional"))
      (node (ref "R43") (pin "1") (pinfunction "1_1") (pintype "passive"))
    )
    (net (code "48") (name "Net-(INJACK-RIGHT)") (class "Default")
      (node (ref "INJACK") (pin "R") (pinfunction "RIGHT_R") (pintype "bidirectional"))
      (node (ref "R44") (pin "1") (pinfunction "1_1") (pintype "passive"))
    )
    (net (code "49") (name "Net-(J2-D-)") (class "Default")
      (node (ref "J2") (pin "2") (pinfunction "D-_2") (pintype "bidirectional"))
      (node (ref "JP3") (pin "1") (pinfunction "1_1") (pintype "passive"))
    )
    (net (code "50") (name "Net-(JP1-Pad2)") (class "Default")
      (node (ref "JP1") (pin "2") (pinfunction "2_2") (pintype "passive"))
      (node (ref "USB/EXT") (pin "3") (pinfunction "3_3") (pintype "passive"))
    )
    (net (code "51") (name "Net-(L1-PadC)") (class "Default")
      (node (ref "L1") (pin "C") (pinfunction "C_C") (pintype "passive"))
      (node (ref "R13") (pin "2") (pinfunction "2_2") (pintype "passive"))
    )
    (net (code "52") (name "Net-(L2-PadC)") (class "Default")
      (node (ref "L2") (pin "C") (pinfunction "C_C") (pintype "passive"))
      (node (ref "R14") (pin "2") (pinfunction "2_2") (pintype "passive"))
    )
    (net (code "53") (name "Net-(ON-P)") (class "Default")
      (node (ref "ON") (pin "2") (pinfunction "P_2") (pintype "passive"))
      (node (ref "USB/EXT") (pin "2") (pinfunction "2_2") (pintype "passive"))
    )
    (net (code "54") (name "Net-(ON-S)") (class "Default")
      (node (ref "C5") (pin "1") (pinfunction "1_1") (pintype "passive"))
      (node (ref "ON") (pin "3") (pinfunction "S_3") (pintype "passive"))
      (node (ref "U$3") (pin "2") (pinfunction "VI_2") (pintype "input"))
      (node (ref "U$3") (pin "4") (pinfunction "VI_4") (pintype "input"))
    )
    (net (code "55") (name "Net-(OUTJACK-LEFT-PadL)") (class "Default")
      (node (ref "OUTJACK") (pin "L") (pinfunction "LEFT_L") (pintype "bidirectional"))
      (node (ref "OUTJACK") (pin "L@1") (pinfunction "LEFT_L@1") (pintype "bidirectional"))
      (node (ref "R46") (pin "1") (pinfunction "1_1") (pintype "passive"))
    )
    (net (code "56") (name "Net-(OUTJACK-RIGHT)") (class "Default")
      (node (ref "OUTJACK") (pin "R") (pinfunction "RIGHT_R") (pintype "bidirectional"))
      (node (ref "R47") (pin "1") (pinfunction "1_1") (pintype "passive"))
    )
    (net (code "57") (name "Net-(PIC32-RA2)") (class "Default")
      (node (ref "8MHZ") (pin "2") (pinfunction "2_2") (pintype "passive"))
      (node (ref "C8") (pin "1") (pinfunction "1_1") (pintype "passive"))
      (node (ref "PIC32") (pin "9") (pinfunction "RA2_9") (pintype "bidirectional"))
    )
    (net (code "58") (name "Net-(PIC32-RA3)") (class "Default")
      (node (ref "8MHZ") (pin "1") (pinfunction "1_1") (pintype "passive"))
      (node (ref "C7") (pin "1") (pinfunction "1_1") (pintype "passive"))
      (node (ref "PIC32") (pin "10") (pinfunction "RA3_10") (pintype "bidirectional"))
    )
    (net (code "59") (name "Net-(PIC32-VCAP)") (class "Default")
      (node (ref "C1") (pin "+") (pinfunction "+_+") (pintype "passive"))
      (node (ref "PIC32") (pin "20") (pinfunction "VCAP_20") (pintype "passive"))
    )
    (net (code "60") (name "Net-(PIC32-~{MCLR})") (class "Default")
      (node (ref "PIC32") (pin "1") (pinfunction "~{MCLR}_1") (pintype "input"))
      (node (ref "R1") (pin "1") (pinfunction "1_1") (pintype "passive"))
    )
    (net (code "61") (name "Net-(Q3-PadB)") (class "Default")
      (node (ref "Q3") (pin "B") (pinfunction "B_B") (pintype "passive"))
      (node (ref "R8") (pin "2") (pinfunction "2_2") (pintype "passive"))
    )
    (net (code "62") (name "Net-(Q3-PadC)") (class "Default")
      (node (ref "Q3") (pin "C") (pinfunction "C_C") (pintype "passive"))
      (node (ref "R7") (pin "1") (pinfunction "1_1") (pintype "passive"))
    )
    (net (code "63") (name "Net-(Q4-PadB)") (class "Default")
      (node (ref "Q4") (pin "B") (pinfunction "B_B") (pintype "passive"))
      (node (ref "R12") (pin "2") (pinfunction "2_2") (pintype "passive"))
    )
    (net (code "64") (name "Net-(Q4-PadC)") (class "Default")
      (node (ref "Q4") (pin "C") (pinfunction "C_C") (pintype "passive"))
      (node (ref "R14") (pin "1") (pinfunction "1_1") (pintype "passive"))
    )
    (net (code "65") (name "Net-(Q5-PadB)") (class "Default")
      (node (ref "Q5") (pin "B") (pinfunction "B_B") (pintype "passive"))
      (node (ref "R11") (pin "2") (pinfunction "2_2") (pintype "passive"))
    )
    (net (code "66") (name "Net-(Q5-PadC)") (class "Default")
      (node (ref "Q5") (pin "C") (pinfunction "C_C") (pintype "passive"))
      (node (ref "R13") (pin "1") (pinfunction "1_1") (pintype "passive"))
    )
    (net (code "67") (name "Net-(RESET-A)") (class "Default")
      (node (ref "R9") (pin "1") (pinfunction "1_1") (pintype "passive"))
      (node (ref "RESET") (pin "1") (pinfunction "A_1") (pintype "passive"))
    )
    (net (code "68") (name "Net-(SW1A-SIG1)") (class "Default")
      (node (ref "R19") (pin "2") (pinfunction "2_2") (pintype "passive"))
      (node (ref "SW1") (pin "1") (pinfunction "SIG1_1") (pintype "passive"))
    )
    (net (code "69") (name "Net-(SW1A-SIG2)") (class "Default")
      (node (ref "R26") (pin "2") (pinfunction "2_2") (pintype "passive"))
      (node (ref "SW1") (pin "3") (pinfunction "SIG2_3") (pintype "passive"))
    )
    (net (code "70") (name "Net-(SW1B-A)") (class "Default")
      (node (ref "R18") (pin "2") (pinfunction "2_2") (pintype "passive"))
      (node (ref "R21") (pin "2") (pinfunction "2_2") (pintype "passive"))
      (node (ref "SW1") (pin "B") (pinfunction "A_B") (pintype "passive"))
    )
    (net (code "71") (name "Net-(VOLUMEA-3)") (class "Default")
      (node (ref "C13") (pin "-") (pinfunction "-_-") (pintype "passive"))
      (node (ref "VOLUME") (pin "P$3") (pinfunction "3_P$3") (pintype "passive"))
    )
    (net (code "72") (name "Vb") (class "Default")
      (node (ref "6004") (pin "3") (pinfunction "+IN_3") (pintype "input"))
      (node (ref "6004") (pin "5") (pinfunction "+IN_5") (pintype "input"))
      (node (ref "C24") (pin "+") (pinfunction "+_+") (pintype "passive"))
      (node (ref "R40") (pin "1") (pinfunction "1_1") (pintype "passive"))
      (node (ref "R41") (pin "2") (pinfunction "2_2") (pintype "passive"))
    )
    (net (code "73") (name "unconnected-(ICSP-Pad6)") (class "Default")
      (node (ref "ICSP") (pin "6") (pinfunction "6_6") (pintype "passive"))
    )
    (net (code "74") (name "unconnected-(J2-ID-Pad4)") (class "Default")
      (node (ref "J2") (pin "4") (pinfunction "ID_4") (pintype "bidirectional"))
    )
    (net (code "75") (name "unconnected-(J2-PadS1)") (class "Default")
      (node (ref "J2") (pin "S1") (pinfunction "S1_S1") (pintype "passive"))
    )
    (net (code "76") (name "unconnected-(J2-PadS2)") (class "Default")
      (node (ref "J2") (pin "S2") (pinfunction "S2_S2") (pintype "passive"))
    )
    (net (code "77") (name "unconnected-(ON-O-Pad1)") (class "Default")
      (node (ref "ON") (pin "1") (pinfunction "O_1") (pintype "passive"))
    )
  )
)
